# a915-enhancer.net
KiCad netlist of a schematic drawn in EAGLE
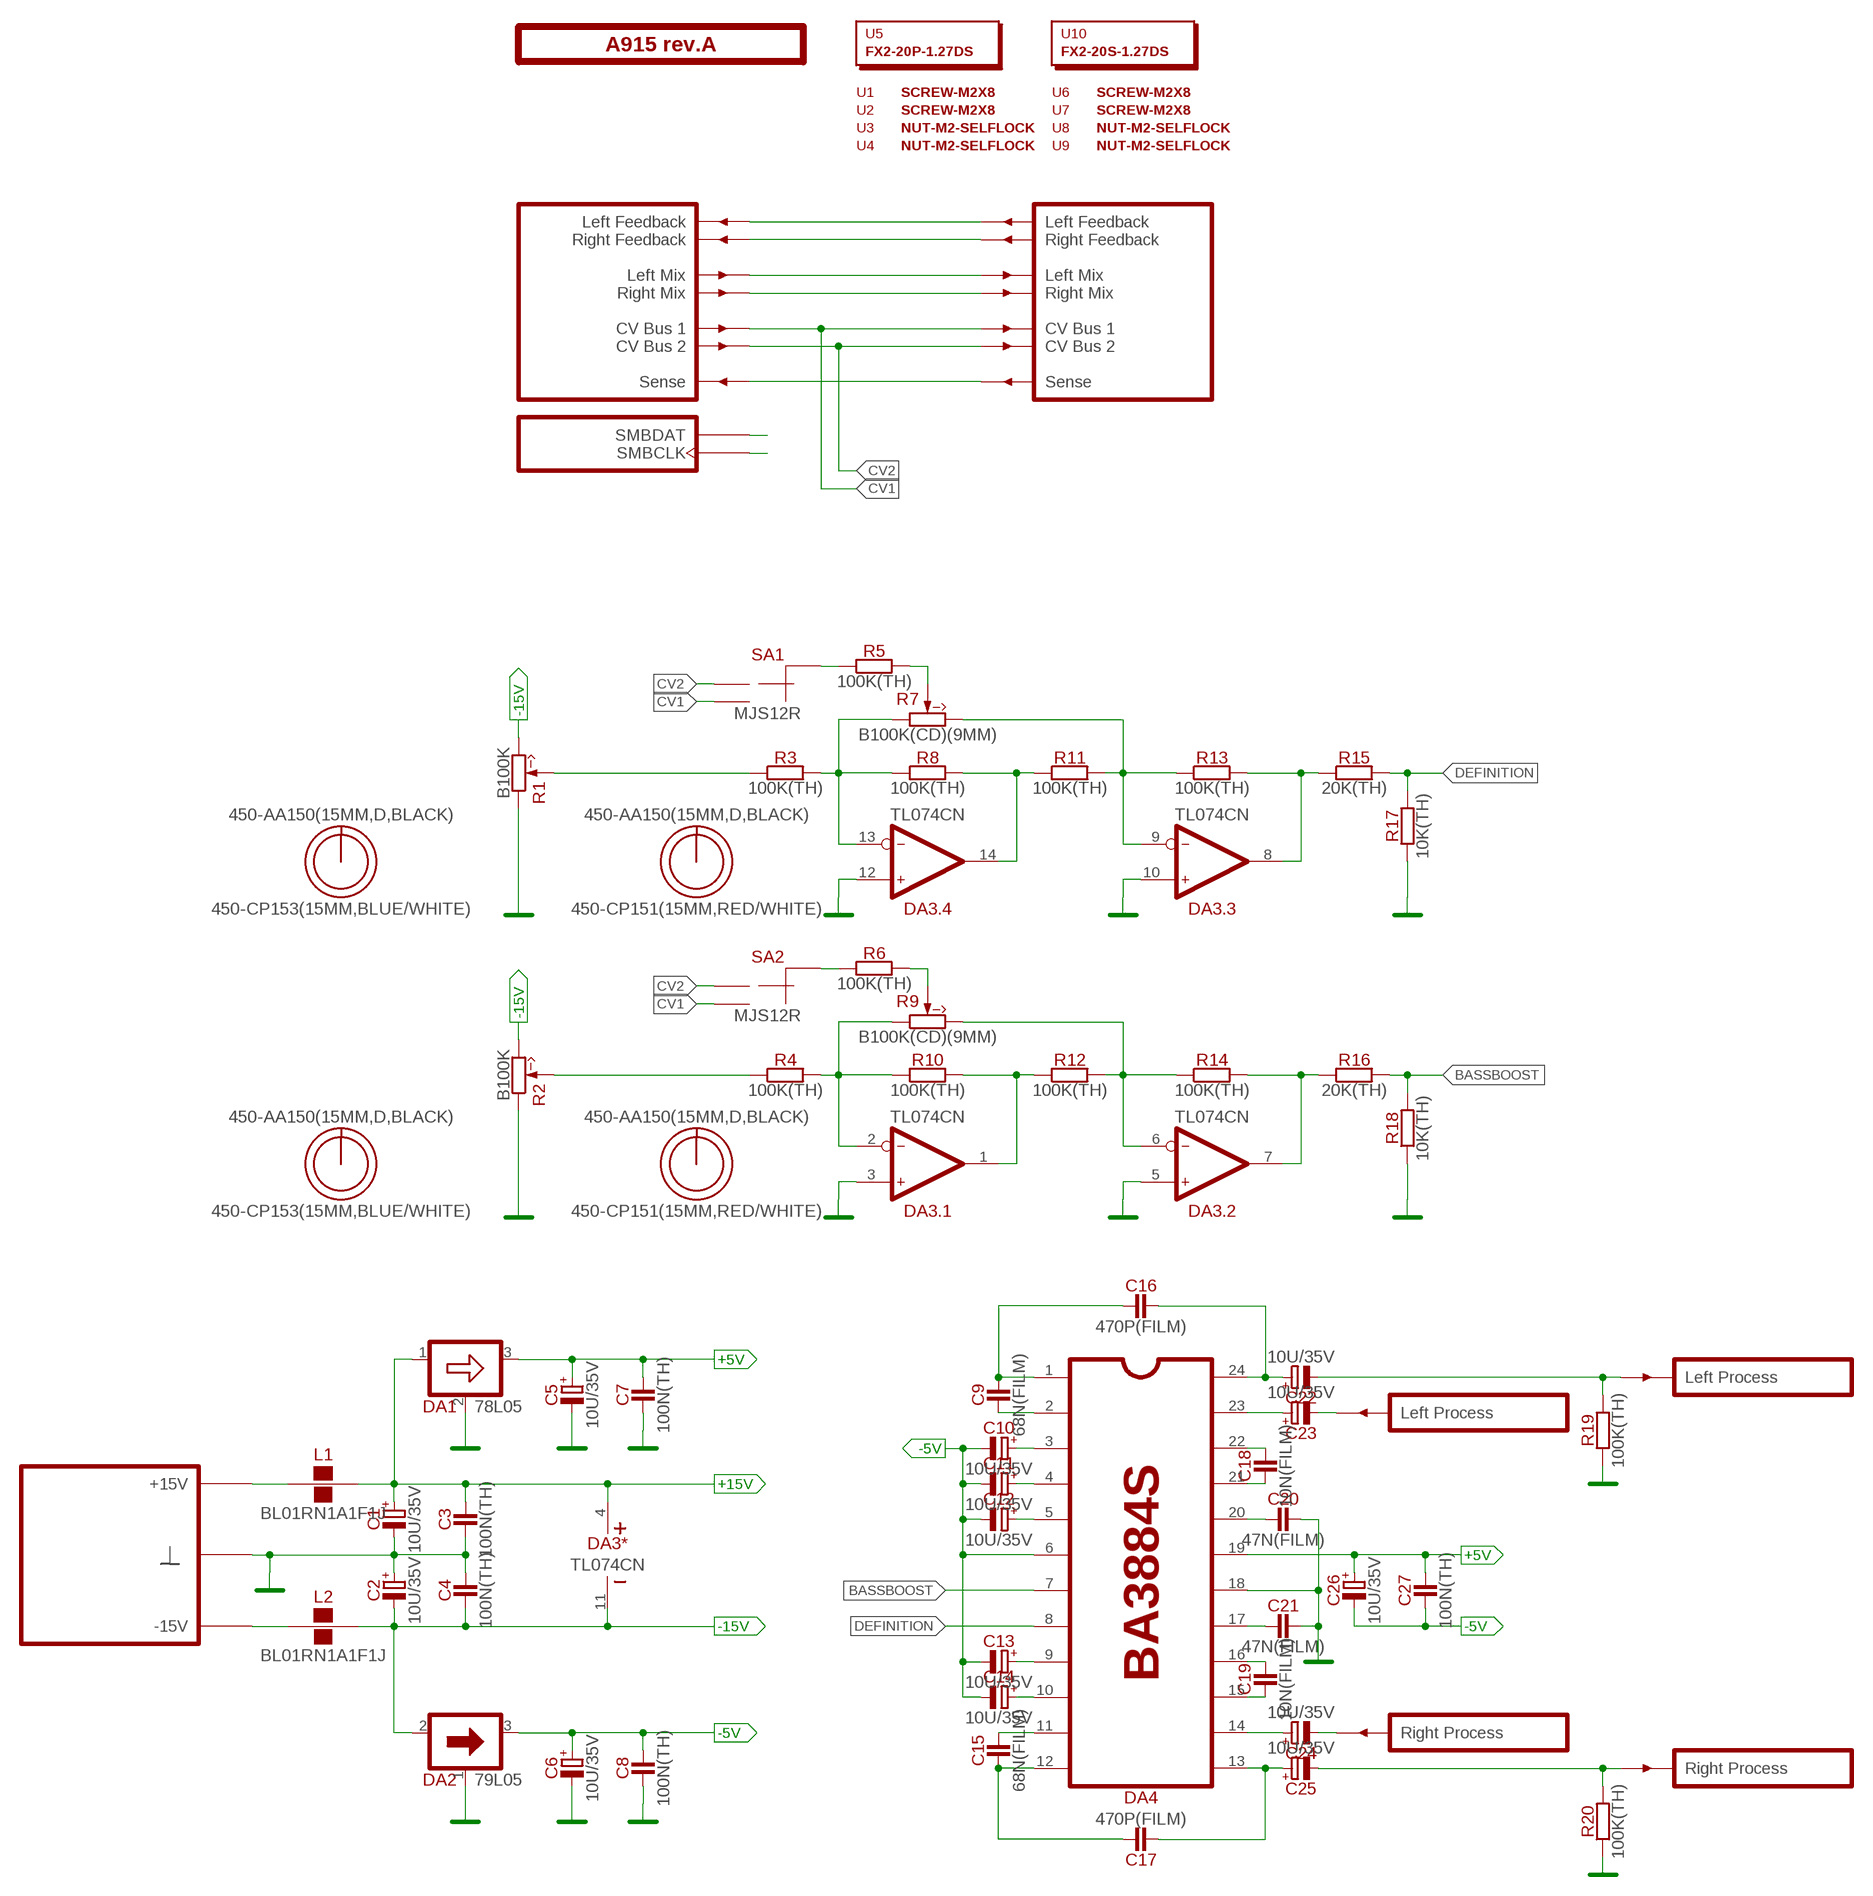
[diagram p0: schematic, sheet 1]

(export (version "E")
  (design (tool "Eeschema 10.0.6"))
  (components
    (comp (ref "C1")
      (value "10U/35V")
      (footprint "eagle-import:E2-5")
      (libsource (lib "eagle-import") (part "?10U/35V"))
    )
    (comp (ref "C2")
      (value "10U/35V")
      (footprint "eagle-import:E2-5")
      (libsource (lib "eagle-import") (part "?10U/35V"))
    )
    (comp (ref "C3")
      (value "100N(TH)")
      (footprint "eagle-import:C050-024X044")
      (libsource (lib "eagle-import") (part "?100N(TH)"))
    )
    (comp (ref "C4")
      (value "100N(TH)")
      (footprint "eagle-import:C050-024X044")
      (libsource (lib "eagle-import") (part "?100N(TH)"))
    )
    (comp (ref "C5")
      (value "10U/35V")
      (footprint "eagle-import:E2-5")
      (libsource (lib "eagle-import") (part "?10U/35V"))
    )
    (comp (ref "C6")
      (value "10U/35V")
      (footprint "eagle-import:E2-5")
      (libsource (lib "eagle-import") (part "?10U/35V"))
    )
    (comp (ref "C7")
      (value "100N(TH)")
      (footprint "eagle-import:C050-024X044")
      (libsource (lib "eagle-import") (part "?100N(TH)"))
    )
    (comp (ref "C8")
      (value "100N(TH)")
      (footprint "eagle-import:C050-024X044")
      (libsource (lib "eagle-import") (part "?100N(TH)"))
    )
    (comp (ref "C9")
      (value "68N(FILM)")
      (footprint "eagle-import:C050-025X075")
      (libsource (lib "eagle-import") (part "?68N(FILM)"))
    )
    (comp (ref "C10")
      (value "10U/35V")
      (footprint "eagle-import:E2-5")
      (libsource (lib "eagle-import") (part "?10U/35V"))
    )
    (comp (ref "C11")
      (value "10U/35V")
      (footprint "eagle-import:E2-5")
      (libsource (lib "eagle-import") (part "?10U/35V"))
    )
    (comp (ref "C12")
      (value "10U/35V")
      (footprint "eagle-import:E2-5")
      (libsource (lib "eagle-import") (part "?10U/35V"))
    )
    (comp (ref "C13")
      (value "10U/35V")
      (footprint "eagle-import:E2-5")
      (libsource (lib "eagle-import") (part "?10U/35V"))
    )
    (comp (ref "C14")
      (value "10U/35V")
      (footprint "eagle-import:E2-5")
      (libsource (lib "eagle-import") (part "?10U/35V"))
    )
    (comp (ref "C15")
      (value "68N(FILM)")
      (footprint "eagle-import:C050-025X075")
      (libsource (lib "eagle-import") (part "?68N(FILM)"))
    )
    (comp (ref "C16")
      (value "470P(FILM)")
      (footprint "eagle-import:C050-055X075")
      (libsource (lib "eagle-import") (part "?470P(FILM)"))
    )
    (comp (ref "C17")
      (value "470P(FILM)")
      (footprint "eagle-import:C050-055X075")
      (libsource (lib "eagle-import") (part "?470P(FILM)"))
    )
    (comp (ref "C18")
      (value "10N(FILM)")
      (footprint "eagle-import:C050-025X075")
      (libsource (lib "eagle-import") (part "?10N(FILM)"))
    )
    (comp (ref "C19")
      (value "10N(FILM)")
      (footprint "eagle-import:C050-025X075")
      (libsource (lib "eagle-import") (part "?10N(FILM)"))
    )
    (comp (ref "C20")
      (value "47N(FILM)")
      (footprint "eagle-import:C050-025X075")
      (libsource (lib "eagle-import") (part "?47N(FILM)"))
    )
    (comp (ref "C21")
      (value "47N(FILM)")
      (footprint "eagle-import:C050-025X075")
      (libsource (lib "eagle-import") (part "?47N(FILM)"))
    )
    (comp (ref "C22")
      (value "10U/35V")
      (footprint "eagle-import:E2-5")
      (libsource (lib "eagle-import") (part "?10U/35V"))
    )
    (comp (ref "C23")
      (value "10U/35V")
      (footprint "eagle-import:E2-5")
      (libsource (lib "eagle-import") (part "?10U/35V"))
    )
    (comp (ref "C24")
      (value "10U/35V")
      (footprint "eagle-import:E2-5")
      (libsource (lib "eagle-import") (part "?10U/35V"))
    )
    (comp (ref "C25")
      (value "10U/35V")
      (footprint "eagle-import:E2-5")
      (libsource (lib "eagle-import") (part "?10U/35V"))
    )
    (comp (ref "C26")
      (value "10U/35V")
      (footprint "eagle-import:E2-5")
      (libsource (lib "eagle-import") (part "?10U/35V"))
    )
    (comp (ref "C27")
      (value "100N(TH)")
      (footprint "eagle-import:C050-024X044")
      (libsource (lib "eagle-import") (part "?100N(TH)"))
    )
    (comp (ref "DA1")
      (value "78L05")
      (footprint "eagle-import:TO92")
      (libsource (lib "eagle-import") (part "78L05"))
    )
    (comp (ref "DA2")
      (value "79L05")
      (footprint "eagle-import:TO92")
      (libsource (lib "eagle-import") (part "79L05"))
    )
    (comp (ref "DA3")
      (value "TL074CN")
      (footprint "eagle-import:DIP-14")
      (libsource (lib "eagle-import") (part "TL074CN"))
    )
    (comp (ref "DA4")
      (value "BA3884S")
      (footprint "eagle-import:SDIP-24")
      (libsource (lib "eagle-import") (part "BA3884S"))
    )
    (comp (ref "L1")
      (value "BL01RN1A1F1J")
      (footprint "eagle-import:BL01RN1A")
      (libsource (lib "eagle-import") (part "BL01RN1A?1F1J"))
    )
    (comp (ref "L2")
      (value "BL01RN1A1F1J")
      (footprint "eagle-import:BL01RN1A")
      (libsource (lib "eagle-import") (part "BL01RN1A?1F1J"))
    )
    (comp (ref "O1")
      (value "450-AA150(15MM,D,BLACK)")
      (footprint "eagle-import:EMPTY")
      (libsource (lib "eagle-import") (part "450-AA?150(15MM,D,BLACK)"))
    )
    (comp (ref "O2")
      (value "450-CP153(15MM,BLUE/WHITE)")
      (footprint "eagle-import:EMPTY")
      (libsource (lib "eagle-import") (part "450-C?P153(15MM,BLUE/WHITE)"))
    )
    (comp (ref "O3")
      (value "450-AA150(15MM,D,BLACK)")
      (footprint "eagle-import:EMPTY")
      (libsource (lib "eagle-import") (part "450-AA?150(15MM,D,BLACK)"))
    )
    (comp (ref "O4")
      (value "450-CP153(15MM,BLUE/WHITE)")
      (footprint "eagle-import:EMPTY")
      (libsource (lib "eagle-import") (part "450-C?P153(15MM,BLUE/WHITE)"))
    )
    (comp (ref "O5")
      (value "450-AA150(15MM,D,BLACK)")
      (footprint "eagle-import:EMPTY")
      (libsource (lib "eagle-import") (part "450-AA?150(15MM,D,BLACK)"))
    )
    (comp (ref "O6")
      (value "450-CP151(15MM,RED/WHITE)")
      (footprint "eagle-import:EMPTY")
      (libsource (lib "eagle-import") (part "450-C?P151(15MM,RED/WHITE)"))
    )
    (comp (ref "O7")
      (value "450-AA150(15MM,D,BLACK)")
      (footprint "eagle-import:EMPTY")
      (libsource (lib "eagle-import") (part "450-AA?150(15MM,D,BLACK)"))
    )
    (comp (ref "O8")
      (value "450-CP151(15MM,RED/WHITE)")
      (footprint "eagle-import:EMPTY")
      (libsource (lib "eagle-import") (part "450-C?P151(15MM,RED/WHITE)"))
    )
    (comp (ref "PCB1")
      (value "A915 rev.A")
      (footprint "eagle-import:ST2-BOARD-50")
      (libsource (lib "eagle-import") (part "ST2-BOARD-?50"))
    )
    (comp (ref "R1")
      (value "B100K")
      (footprint "eagle-import:RV11-SINGLE")
      (libsource (lib "eagle-import") (part "?B100K"))
    )
    (comp (ref "R2")
      (value "B100K")
      (footprint "eagle-import:RV11-SINGLE")
      (libsource (lib "eagle-import") (part "?B100K"))
    )
    (comp (ref "R3")
      (value "100K(TH)")
      (footprint "eagle-import:R-0207_10")
      (libsource (lib "eagle-import") (part "?100K(TH)"))
    )
    (comp (ref "R4")
      (value "100K(TH)")
      (footprint "eagle-import:R-0207_10")
      (libsource (lib "eagle-import") (part "?100K(TH)"))
    )
    (comp (ref "R5")
      (value "100K(TH)")
      (footprint "eagle-import:R-0207_10")
      (libsource (lib "eagle-import") (part "?100K(TH)"))
    )
    (comp (ref "R6")
      (value "100K(TH)")
      (footprint "eagle-import:R-0207_10")
      (libsource (lib "eagle-import") (part "?100K(TH)"))
    )
    (comp (ref "R7")
      (value "B100K(CD)(9MM)")
      (footprint "eagle-import:RV09-SINGLE")
      (libsource (lib "eagle-import") (part "?B100K(CD)(9MM)"))
    )
    (comp (ref "R8")
      (value "100K(TH)")
      (footprint "eagle-import:R-0207_10")
      (libsource (lib "eagle-import") (part "?100K(TH)"))
    )
    (comp (ref "R9")
      (value "B100K(CD)(9MM)")
      (footprint "eagle-import:RV09-SINGLE")
      (libsource (lib "eagle-import") (part "?B100K(CD)(9MM)"))
    )
    (comp (ref "R10")
      (value "100K(TH)")
      (footprint "eagle-import:R-0207_10")
      (libsource (lib "eagle-import") (part "?100K(TH)"))
    )
    (comp (ref "R11")
      (value "100K(TH)")
      (footprint "eagle-import:R-0207_10")
      (libsource (lib "eagle-import") (part "?100K(TH)"))
    )
    (comp (ref "R12")
      (value "100K(TH)")
      (footprint "eagle-import:R-0207_10")
      (libsource (lib "eagle-import") (part "?100K(TH)"))
    )
    (comp (ref "R13")
      (value "100K(TH)")
      (footprint "eagle-import:R-0207_10")
      (libsource (lib "eagle-import") (part "?100K(TH)"))
    )
    (comp (ref "R14")
      (value "100K(TH)")
      (footprint "eagle-import:R-0207_10")
      (libsource (lib "eagle-import") (part "?100K(TH)"))
    )
    (comp (ref "R15")
      (value "20K(TH)")
      (footprint "eagle-import:R-0207_10")
      (libsource (lib "eagle-import") (part "?20K(TH)"))
    )
    (comp (ref "R16")
      (value "20K(TH)")
      (footprint "eagle-import:R-0207_10")
      (libsource (lib "eagle-import") (part "?20K(TH)"))
    )
    (comp (ref "R17")
      (value "10K(TH)")
      (footprint "eagle-import:R-0207_10")
      (libsource (lib "eagle-import") (part "?10K(TH)"))
    )
    (comp (ref "R18")
      (value "10K(TH)")
      (footprint "eagle-import:R-0207_10")
      (libsource (lib "eagle-import") (part "?10K(TH)"))
    )
    (comp (ref "R19")
      (value "100K(TH)")
      (footprint "eagle-import:R-0207_10")
      (libsource (lib "eagle-import") (part "?100K(TH)"))
    )
    (comp (ref "R20")
      (value "100K(TH)")
      (footprint "eagle-import:R-0207_10")
      (libsource (lib "eagle-import") (part "?100K(TH)"))
    )
    (comp (ref "SA1")
      (value "MJS12R")
      (footprint "eagle-import:APEM-MJS12R")
      (libsource (lib "eagle-import") (part "MJS12R"))
    )
    (comp (ref "SA2")
      (value "MJS12R")
      (footprint "eagle-import:APEM-MJS12R")
      (libsource (lib "eagle-import") (part "MJS12R"))
    )
    (comp (ref "U1")
      (value "SCREW-M2X8")
      (footprint "eagle-import:EMPTY")
      (libsource (lib "eagle-import") (part "?SCREW-M2X8"))
    )
    (comp (ref "U2")
      (value "SCREW-M2X8")
      (footprint "eagle-import:EMPTY")
      (libsource (lib "eagle-import") (part "?SCREW-M2X8"))
    )
    (comp (ref "U3")
      (value "NUT-M2-SELFLOCK")
      (footprint "eagle-import:EMPTY")
      (libsource (lib "eagle-import") (part "?NUT-M2-SELFLOCK"))
    )
    (comp (ref "U4")
      (value "NUT-M2-SELFLOCK")
      (footprint "eagle-import:EMPTY")
      (libsource (lib "eagle-import") (part "?NUT-M2-SELFLOCK"))
    )
    (comp (ref "U5")
      (value "FX2-20P-1.27DS")
      (footprint "eagle-import:EMPTY")
      (libsource (lib "eagle-import") (part "?FX2-20P-1.27DS"))
    )
    (comp (ref "U6")
      (value "SCREW-M2X8")
      (footprint "eagle-import:EMPTY")
      (libsource (lib "eagle-import") (part "?SCREW-M2X8"))
    )
    (comp (ref "U7")
      (value "SCREW-M2X8")
      (footprint "eagle-import:EMPTY")
      (libsource (lib "eagle-import") (part "?SCREW-M2X8"))
    )
    (comp (ref "U8")
      (value "NUT-M2-SELFLOCK")
      (footprint "eagle-import:EMPTY")
      (libsource (lib "eagle-import") (part "?NUT-M2-SELFLOCK"))
    )
    (comp (ref "U9")
      (value "NUT-M2-SELFLOCK")
      (footprint "eagle-import:EMPTY")
      (libsource (lib "eagle-import") (part "?NUT-M2-SELFLOCK"))
    )
    (comp (ref "U10")
      (value "FX2-20S-1.27DS")
      (footprint "eagle-import:EMPTY")
      (libsource (lib "eagle-import") (part "?FX2-20S-1.27DS"))
    )
  )
  (nets
    (net (code "1") (name "+5V") (class "Default")
      (node (ref "C26") (pin "+") (pinfunction "+_+") (pintype "passive"))
      (node (ref "C27") (pin "2") (pinfunction "2_2") (pintype "passive"))
      (node (ref "C5") (pin "+") (pinfunction "+_+") (pintype "passive"))
      (node (ref "C7") (pin "2") (pinfunction "2_2") (pintype "passive"))
      (node (ref "DA1") (pin "3") (pinfunction "OUT_3") (pintype "power_in"))
      (node (ref "DA4") (pin "19") (pinfunction "19_19") (pintype "bidirectional"))
    )
    (net (code "2") (name "+15V") (class "Default")
      (node (ref "C1") (pin "+") (pinfunction "+_+") (pintype "passive"))
      (node (ref "C3") (pin "2") (pinfunction "2_2") (pintype "passive"))
      (node (ref "DA1") (pin "1") (pinfunction "IN_1") (pintype "power_in"))
      (node (ref "DA3") (pin "4") (pinfunction "V+_4") (pintype "power_in"))
      (node (ref "L1") (pin "2") (pinfunction "2_2") (pintype "passive"))
    )
    (net (code "3") (name "-5V") (class "Default")
      (node (ref "C10") (pin "-") (pinfunction "-_-") (pintype "passive"))
      (node (ref "C11") (pin "-") (pinfunction "-_-") (pintype "passive"))
      (node (ref "C12") (pin "-") (pinfunction "-_-") (pintype "passive"))
      (node (ref "C13") (pin "-") (pinfunction "-_-") (pintype "passive"))
      (node (ref "C14") (pin "-") (pinfunction "-_-") (pintype "passive"))
      (node (ref "C26") (pin "-") (pinfunction "-_-") (pintype "passive"))
      (node (ref "C27") (pin "1") (pinfunction "1_1") (pintype "passive"))
      (node (ref "C6") (pin "+") (pinfunction "+_+") (pintype "passive"))
      (node (ref "C8") (pin "2") (pinfunction "2_2") (pintype "passive"))
      (node (ref "DA2") (pin "3") (pinfunction "OUT_3") (pintype "power_in"))
      (node (ref "DA4") (pin "6") (pinfunction "6_6") (pintype "bidirectional"))
    )
    (net (code "4") (name "-15V") (class "Default")
      (node (ref "C2") (pin "-") (pinfunction "-_-") (pintype "passive"))
      (node (ref "C4") (pin "1") (pinfunction "1_1") (pintype "passive"))
      (node (ref "DA2") (pin "2") (pinfunction "IN_2") (pintype "power_in"))
      (node (ref "DA3") (pin "11") (pinfunction "V-_11") (pintype "power_in"))
      (node (ref "L2") (pin "2") (pinfunction "2_2") (pintype "passive"))
      (node (ref "R1") (pin "3") (pinfunction "CW_3") (pintype "passive"))
      (node (ref "R2") (pin "3") (pinfunction "CW_3") (pintype "passive"))
    )
    (net (code "5") (name "BASSBOOST") (class "Default")
      (node (ref "DA4") (pin "7") (pinfunction "7_7") (pintype "bidirectional"))
      (node (ref "R16") (pin "2") (pinfunction "2_2") (pintype "passive"))
      (node (ref "R18") (pin "2") (pinfunction "2_2") (pintype "passive"))
    )
    (net (code "6") (name "CV1") (class "Default")
      (node (ref "PCB1") (pin "ACV1") (pinfunction "CV1_ACV1") (pintype "bidirectional"))
      (node (ref "PCB1") (pin "ACV1'") (pinfunction "CV1'_ACV1'") (pintype "bidirectional"))
      (node (ref "SA1") (pin "NO") (pinfunction "2_NO") (pintype "passive"))
      (node (ref "SA2") (pin "NO") (pinfunction "2_NO") (pintype "passive"))
    )
    (net (code "7") (name "CV2") (class "Default")
      (node (ref "PCB1") (pin "ACV2") (pinfunction "CV2_ACV2") (pintype "bidirectional"))
      (node (ref "PCB1") (pin "ACV2'") (pinfunction "CV2'_ACV2'") (pintype "bidirectional"))
      (node (ref "SA1") (pin "NC") (pinfunction "1_NC") (pintype "passive"))
      (node (ref "SA2") (pin "NC") (pinfunction "1_NC") (pintype "passive"))
    )
    (net (code "8") (name "DEFINITION") (class "Default")
      (node (ref "DA4") (pin "8") (pinfunction "8_8") (pintype "bidirectional"))
      (node (ref "R15") (pin "2") (pinfunction "2_2") (pintype "passive"))
      (node (ref "R17") (pin "2") (pinfunction "2_2") (pintype "passive"))
    )
    (net (code "9") (name "GND") (class "Default")
      (node (ref "C1") (pin "-") (pinfunction "-_-") (pintype "passive"))
      (node (ref "C2") (pin "+") (pinfunction "+_+") (pintype "passive"))
      (node (ref "C20") (pin "2") (pinfunction "2_2") (pintype "passive"))
      (node (ref "C21") (pin "2") (pinfunction "2_2") (pintype "passive"))
      (node (ref "C3") (pin "1") (pinfunction "1_1") (pintype "passive"))
      (node (ref "C4") (pin "2") (pinfunction "2_2") (pintype "passive"))
      (node (ref "C5") (pin "-") (pinfunction "-_-") (pintype "passive"))
      (node (ref "C6") (pin "-") (pinfunction "-_-") (pintype "passive"))
      (node (ref "C7") (pin "1") (pinfunction "1_1") (pintype "passive"))
      (node (ref "C8") (pin "1") (pinfunction "1_1") (pintype "passive"))
      (node (ref "DA1") (pin "2") (pinfunction "GND_2") (pintype "power_in"))
      (node (ref "DA2") (pin "1") (pinfunction "GND_1") (pintype "power_in"))
      (node (ref "DA3") (pin "10") (pinfunction "IN+_10") (pintype "input"))
      (node (ref "DA3") (pin "12") (pinfunction "IN+_12") (pintype "input"))
      (node (ref "DA3") (pin "3") (pinfunction "IN+_3") (pintype "input"))
      (node (ref "DA3") (pin "5") (pinfunction "IN+_5") (pintype "input"))
      (node (ref "DA4") (pin "18") (pinfunction "18_18") (pintype "bidirectional"))
      (node (ref "PCB1") (pin "B4") (pinfunction "GND_B4") (pintype "bidirectional"))
      (node (ref "PCB1") (pin "B4'") (pinfunction "GND_B4'") (pintype "bidirectional"))
      (node (ref "PCB1") (pin "B5") (pinfunction "GND_B5") (pintype "bidirectional"))
      (node (ref "PCB1") (pin "B5'") (pinfunction "GND_B5'") (pintype "bidirectional"))
      (node (ref "PCB1") (pin "B6") (pinfunction "GND_B6") (pintype "bidirectional"))
      (node (ref "PCB1") (pin "B6'") (pinfunction "GND_B6'") (pintype "bidirectional"))
      (node (ref "PCB1") (pin "B7") (pinfunction "GND_B7") (pintype "bidirectional"))
      (node (ref "PCB1") (pin "B7'") (pinfunction "GND_B7'") (pintype "bidirectional"))
      (node (ref "PCB1") (pin "B8") (pinfunction "GND_B8") (pintype "bidirectional"))
      (node (ref "PCB1") (pin "B8'") (pinfunction "GND_B8'") (pintype "bidirectional"))
      (node (ref "R1") (pin "1") (pinfunction "CCW_1") (pintype "passive"))
      (node (ref "R17") (pin "1") (pinfunction "1_1") (pintype "passive"))
      (node (ref "R18") (pin "1") (pinfunction "1_1") (pintype "passive"))
      (node (ref "R19") (pin "1") (pinfunction "1_1") (pintype "passive"))
      (node (ref "R2") (pin "1") (pinfunction "CCW_1") (pintype "passive"))
      (node (ref "R20") (pin "1") (pinfunction "1_1") (pintype "passive"))
    )
    (net (code "10") (name "Net-(C9-Pad1)") (class "Default")
      (node (ref "C9") (pin "1") (pinfunction "1_1") (pintype "passive"))
      (node (ref "DA4") (pin "2") (pinfunction "2_2") (pintype "bidirectional"))
    )
    (net (code "11") (name "Net-(C10-Pad+)") (class "Default")
      (node (ref "C10") (pin "+") (pinfunction "+_+") (pintype "passive"))
      (node (ref "DA4") (pin "3") (pinfunction "3_3") (pintype "bidirectional"))
    )
    (net (code "12") (name "Net-(C11-Pad+)") (class "Default")
      (node (ref "C11") (pin "+") (pinfunction "+_+") (pintype "passive"))
      (node (ref "DA4") (pin "4") (pinfunction "4_4") (pintype "bidirectional"))
    )
    (net (code "13") (name "Net-(C12-Pad+)") (class "Default")
      (node (ref "C12") (pin "+") (pinfunction "+_+") (pintype "passive"))
      (node (ref "DA4") (pin "5") (pinfunction "5_5") (pintype "bidirectional"))
    )
    (net (code "14") (name "Net-(C13-Pad+)") (class "Default")
      (node (ref "C13") (pin "+") (pinfunction "+_+") (pintype "passive"))
      (node (ref "DA4") (pin "9") (pinfunction "9_9") (pintype "bidirectional"))
    )
    (net (code "15") (name "Net-(C14-Pad+)") (class "Default")
      (node (ref "C14") (pin "+") (pinfunction "+_+") (pintype "passive"))
      (node (ref "DA4") (pin "10") (pinfunction "10_10") (pintype "bidirectional"))
    )
    (net (code "16") (name "Net-(C15-Pad1)") (class "Default")
      (node (ref "C15") (pin "1") (pinfunction "1_1") (pintype "passive"))
      (node (ref "C17") (pin "2") (pinfunction "2_2") (pintype "passive"))
      (node (ref "DA4") (pin "12") (pinfunction "12_12") (pintype "bidirectional"))
    )
    (net (code "17") (name "Net-(C15-Pad2)") (class "Default")
      (node (ref "C15") (pin "2") (pinfunction "2_2") (pintype "passive"))
      (node (ref "DA4") (pin "11") (pinfunction "11_11") (pintype "bidirectional"))
    )
    (net (code "18") (name "Net-(C16-Pad1)") (class "Default")
      (node (ref "C16") (pin "1") (pinfunction "1_1") (pintype "passive"))
      (node (ref "C9") (pin "2") (pinfunction "2_2") (pintype "passive"))
      (node (ref "DA4") (pin "1") (pinfunction "1_1") (pintype "bidirectional"))
    )
    (net (code "19") (name "Net-(C16-Pad2)") (class "Default")
      (node (ref "C16") (pin "2") (pinfunction "2_2") (pintype "passive"))
      (node (ref "C22") (pin "+") (pinfunction "+_+") (pintype "passive"))
      (node (ref "DA4") (pin "24") (pinfunction "24_24") (pintype "bidirectional"))
    )
    (net (code "20") (name "Net-(C17-Pad1)") (class "Default")
      (node (ref "C17") (pin "1") (pinfunction "1_1") (pintype "passive"))
      (node (ref "C25") (pin "+") (pinfunction "+_+") (pintype "passive"))
      (node (ref "DA4") (pin "13") (pinfunction "13_13") (pintype "bidirectional"))
    )
    (net (code "21") (name "Net-(C18-Pad1)") (class "Default")
      (node (ref "C18") (pin "1") (pinfunction "1_1") (pintype "passive"))
      (node (ref "DA4") (pin "21") (pinfunction "21_21") (pintype "bidirectional"))
    )
    (net (code "22") (name "Net-(C18-Pad2)") (class "Default")
      (node (ref "C18") (pin "2") (pinfunction "2_2") (pintype "passive"))
      (node (ref "DA4") (pin "22") (pinfunction "22_22") (pintype "bidirectional"))
    )
    (net (code "23") (name "Net-(C19-Pad1)") (class "Default")
      (node (ref "C19") (pin "1") (pinfunction "1_1") (pintype "passive"))
      (node (ref "DA4") (pin "15") (pinfunction "15_15") (pintype "bidirectional"))
    )
    (net (code "24") (name "Net-(C19-Pad2)") (class "Default")
      (node (ref "C19") (pin "2") (pinfunction "2_2") (pintype "passive"))
      (node (ref "DA4") (pin "16") (pinfunction "16_16") (pintype "bidirectional"))
    )
    (net (code "25") (name "Net-(C20-Pad1)") (class "Default")
      (node (ref "C20") (pin "1") (pinfunction "1_1") (pintype "passive"))
      (node (ref "DA4") (pin "20") (pinfunction "20_20") (pintype "bidirectional"))
    )
    (net (code "26") (name "Net-(C21-Pad1)") (class "Default")
      (node (ref "C21") (pin "1") (pinfunction "1_1") (pintype "passive"))
      (node (ref "DA4") (pin "17") (pinfunction "17_17") (pintype "bidirectional"))
    )
    (net (code "27") (name "Net-(C23-Pad+)") (class "Default")
      (node (ref "C23") (pin "+") (pinfunction "+_+") (pintype "passive"))
      (node (ref "DA4") (pin "23") (pinfunction "23_23") (pintype "bidirectional"))
    )
    (net (code "28") (name "Net-(C24-Pad+)") (class "Default")
      (node (ref "C24") (pin "+") (pinfunction "+_+") (pintype "passive"))
      (node (ref "DA4") (pin "14") (pinfunction "14_14") (pintype "bidirectional"))
    )
    (net (code "29") (name "Net-(DA3B-IN-)") (class "Default")
      (node (ref "DA3") (pin "2") (pinfunction "IN-_2") (pintype "input"))
      (node (ref "R10") (pin "1") (pinfunction "1_1") (pintype "passive"))
      (node (ref "R4") (pin "2") (pinfunction "2_2") (pintype "passive"))
      (node (ref "R9") (pin "1") (pinfunction "CCW_1") (pintype "passive"))
    )
    (net (code "30") (name "Net-(DA3B-OUT)") (class "Default")
      (node (ref "DA3") (pin "1") (pinfunction "OUT_1") (pintype "output"))
      (node (ref "R10") (pin "2") (pinfunction "2_2") (pintype "passive"))
      (node (ref "R12") (pin "1") (pinfunction "1_1") (pintype "passive"))
    )
    (net (code "31") (name "Net-(DA3C-IN-)") (class "Default")
      (node (ref "DA3") (pin "6") (pinfunction "IN-_6") (pintype "input"))
      (node (ref "R12") (pin "2") (pinfunction "2_2") (pintype "passive"))
      (node (ref "R14") (pin "1") (pinfunction "1_1") (pintype "passive"))
      (node (ref "R9") (pin "3") (pinfunction "CW_3") (pintype "passive"))
    )
    (net (code "32") (name "Net-(DA3C-OUT)") (class "Default")
      (node (ref "DA3") (pin "7") (pinfunction "OUT_7") (pintype "output"))
      (node (ref "R14") (pin "2") (pinfunction "2_2") (pintype "passive"))
      (node (ref "R16") (pin "1") (pinfunction "1_1") (pintype "passive"))
    )
    (net (code "33") (name "Net-(DA3D-IN-)") (class "Default")
      (node (ref "DA3") (pin "9") (pinfunction "IN-_9") (pintype "input"))
      (node (ref "R11") (pin "2") (pinfunction "2_2") (pintype "passive"))
      (node (ref "R13") (pin "1") (pinfunction "1_1") (pintype "passive"))
      (node (ref "R7") (pin "3") (pinfunction "CW_3") (pintype "passive"))
    )
    (net (code "34") (name "Net-(DA3D-OUT)") (class "Default")
      (node (ref "DA3") (pin "8") (pinfunction "OUT_8") (pintype "output"))
      (node (ref "R13") (pin "2") (pinfunction "2_2") (pintype "passive"))
      (node (ref "R15") (pin "1") (pinfunction "1_1") (pintype "passive"))
    )
    (net (code "35") (name "Net-(DA3E-IN-)") (class "Default")
      (node (ref "DA3") (pin "13") (pinfunction "IN-_13") (pintype "input"))
      (node (ref "R3") (pin "2") (pinfunction "2_2") (pintype "passive"))
      (node (ref "R7") (pin "1") (pinfunction "CCW_1") (pintype "passive"))
      (node (ref "R8") (pin "1") (pinfunction "1_1") (pintype "passive"))
    )
    (net (code "36") (name "Net-(DA3E-OUT)") (class "Default")
      (node (ref "DA3") (pin "14") (pinfunction "OUT_14") (pintype "output"))
      (node (ref "R11") (pin "1") (pinfunction "1_1") (pintype "passive"))
      (node (ref "R8") (pin "2") (pinfunction "2_2") (pintype "passive"))
    )
    (net (code "37") (name "Net-(L1-Pad1)") (class "Default")
      (node (ref "L1") (pin "1") (pinfunction "1_1") (pintype "passive"))
      (node (ref "PCB1") (pin "A+15") (pinfunction "P+15V_A+15") (pintype "bidirectional"))
      (node (ref "PCB1") (pin "A+15'") (pinfunction "P+15V_A+15'") (pintype "bidirectional"))
      (node (ref "PCB1") (pin "B+15") (pinfunction "P+15V_B+15") (pintype "bidirectional"))
      (node (ref "PCB1") (pin "B+15'") (pinfunction "P+15V_B+15'") (pintype "bidirectional"))
    )
    (net (code "38") (name "Net-(L2-Pad1)") (class "Default")
      (node (ref "L2") (pin "1") (pinfunction "1_1") (pintype "passive"))
      (node (ref "PCB1") (pin "A-15") (pinfunction "P-15V_A-15") (pintype "bidirectional"))
      (node (ref "PCB1") (pin "A-15'") (pinfunction "P-15V_A-15'") (pintype "bidirectional"))
      (node (ref "PCB1") (pin "B-15") (pinfunction "P-15V_B-15") (pintype "bidirectional"))
      (node (ref "PCB1") (pin "B-15'") (pinfunction "P-15V_B-15'") (pintype "bidirectional"))
    )
    (net (code "39") (name "Net-(PCB1B-INL)") (class "Default")
      (node (ref "C23") (pin "-") (pinfunction "-_-") (pintype "passive"))
      (node (ref "PCB1") (pin "BINL") (pinfunction "INL_BINL") (pintype "bidirectional"))
    )
    (net (code "40") (name "Net-(PCB1C-INR)") (class "Default")
      (node (ref "C24") (pin "-") (pinfunction "-_-") (pintype "passive"))
      (node (ref "PCB1") (pin "BINR") (pinfunction "INR_BINR") (pintype "bidirectional"))
    )
    (net (code "41") (name "Net-(PCB1D-OUTL)") (class "Default")
      (node (ref "C22") (pin "-") (pinfunction "-_-") (pintype "passive"))
      (node (ref "PCB1") (pin "BOUTL'") (pinfunction "OUTL_BOUTL'") (pintype "bidirectional"))
      (node (ref "R19") (pin "2") (pinfunction "2_2") (pintype "passive"))
    )
    (net (code "42") (name "Net-(PCB1E-OUTR)") (class "Default")
      (node (ref "C25") (pin "-") (pinfunction "-_-") (pintype "passive"))
      (node (ref "PCB1") (pin "BOUTR'") (pinfunction "OUTR_BOUTR'") (pintype "bidirectional"))
      (node (ref "R20") (pin "2") (pinfunction "2_2") (pintype "passive"))
    )
    (net (code "43") (name "Net-(PCB1F-LFBK)") (class "Default")
      (node (ref "PCB1") (pin "ALFBK") (pinfunction "LFBK_ALFBK") (pintype "bidirectional"))
      (node (ref "PCB1") (pin "ALFBK'") (pinfunction "LFBK'_ALFBK'") (pintype "bidirectional"))
    )
    (net (code "44") (name "Net-(PCB1F-LMIX)") (class "Default")
      (node (ref "PCB1") (pin "ALMIX") (pinfunction "LMIX_ALMIX") (pintype "bidirectional"))
      (node (ref "PCB1") (pin "ALMIX'") (pinfunction "LMIX'_ALMIX'") (pintype "bidirectional"))
    )
    (net (code "45") (name "Net-(PCB1F-RFBK)") (class "Default")
      (node (ref "PCB1") (pin "ARFBK") (pinfunction "RFBK_ARFBK") (pintype "bidirectional"))
      (node (ref "PCB1") (pin "ARFBK'") (pinfunction "RFBK'_ARFBK'") (pintype "bidirectional"))
    )
    (net (code "46") (name "Net-(PCB1F-RMIX)") (class "Default")
      (node (ref "PCB1") (pin "ARMIX") (pinfunction "RMIX_ARMIX") (pintype "bidirectional"))
      (node (ref "PCB1") (pin "ARMIX'") (pinfunction "RMIX'_ARMIX'") (pintype "bidirectional"))
    )
    (net (code "47") (name "Net-(PCB1F-SENSE)") (class "Default")
      (node (ref "PCB1") (pin "BSENSE") (pinfunction "SENSE_BSENSE") (pintype "bidirectional"))
      (node (ref "PCB1") (pin "BSENSE'") (pinfunction "SENSE'_BSENSE'") (pintype "bidirectional"))
    )
    (net (code "48") (name "Net-(PCB1H-SMBCLK-PadASMBCLK')") (class "Default")
      (node (ref "PCB1") (pin "ASMBCLK") (pinfunction "SMBCLK_ASMBCLK") (pintype "bidirectional"))
      (node (ref "PCB1") (pin "ASMBCLK'") (pinfunction "SMBCLK_ASMBCLK'") (pintype "bidirectional"))
    )
    (net (code "49") (name "Net-(PCB1H-SMBDAT-PadASMBDAT')") (class "Default")
      (node (ref "PCB1") (pin "ASMBDAT") (pinfunction "SMBDAT_ASMBDAT") (pintype "bidirectional"))
      (node (ref "PCB1") (pin "ASMBDAT'") (pinfunction "SMBDAT_ASMBDAT'") (pintype "bidirectional"))
    )
    (net (code "50") (name "Net-(R1-W)") (class "Default")
      (node (ref "R1") (pin "2") (pinfunction "W_2") (pintype "passive"))
      (node (ref "R3") (pin "1") (pinfunction "1_1") (pintype "passive"))
    )
    (net (code "51") (name "Net-(R2-W)") (class "Default")
      (node (ref "R2") (pin "2") (pinfunction "W_2") (pintype "passive"))
      (node (ref "R4") (pin "1") (pinfunction "1_1") (pintype "passive"))
    )
    (net (code "52") (name "Net-(R7-W)") (class "Default")
      (node (ref "R5") (pin "2") (pinfunction "2_2") (pintype "passive"))
      (node (ref "R7") (pin "2") (pinfunction "W_2") (pintype "passive"))
    )
    (net (code "53") (name "Net-(R9-W)") (class "Default")
      (node (ref "R6") (pin "2") (pinfunction "2_2") (pintype "passive"))
      (node (ref "R9") (pin "2") (pinfunction "W_2") (pintype "passive"))
    )
    (net (code "54") (name "Net-(SA1-CM)") (class "Default")
      (node (ref "R5") (pin "1") (pinfunction "1_1") (pintype "passive"))
      (node (ref "SA1") (pin "C") (pinfunction "CM_C") (pintype "passive"))
    )
    (net (code "55") (name "Net-(SA2-CM)") (class "Default")
      (node (ref "R6") (pin "1") (pinfunction "1_1") (pintype "passive"))
      (node (ref "SA2") (pin "C") (pinfunction "CM_C") (pintype "passive"))
    )
  )
)
